# CAN_5V.net
KiCad netlist of a schematic drawn in Altium Designer
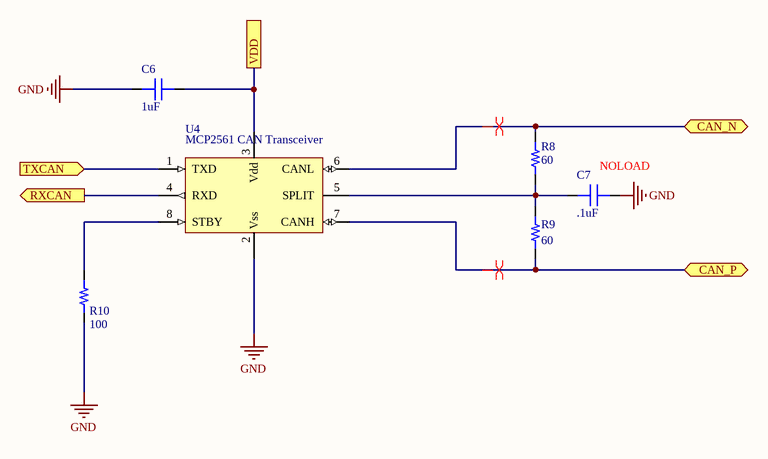
[diagram p0: CAN_5V.SchDoc]

(export (version "E")
  (design (tool "Eeschema 10.0.6"))
  (components
    (comp (ref "C6")
      (value "capacitor")
      (footprint "0603")
      (description "Generic 0603 capacitor")
      (fields (field (name "CAPACITANCE") "1uF") (field (name "VOLTAGE") "50"))
      (libsource (lib "altlib") (part "capacitor"))
    )
    (comp (ref "C7")
      (value "capacitor")
      (footprint "0603")
      (description "Generic 0603 capacitor")
      (fields (field (name "CAPACITANCE") ".1uF") (field (name "VOLTAGE") "50"))
      (libsource (lib "altlib") (part "capacitor"))
    )
    (comp (ref "R8")
      (value "60")
      (footprint "RES 0603/1608")
      (fields (field (name "RESISTANCE") "60"))
      (libsource (lib "altlib") (part "Resistor"))
    )
    (comp (ref "R9")
      (value "60")
      (footprint "RES 0603/1608")
      (fields (field (name "RESISTANCE") "60"))
      (libsource (lib "altlib") (part "Resistor"))
    )
    (comp (ref "R10")
      (value "100")
      (footprint "RES 0603/1608")
      (fields (field (name "RESISTANCE") "100"))
      (libsource (lib "altlib") (part "Resistor"))
    )
    (comp (ref "U4")
      (value "MCP2561 CAN Transceiver")
      (footprint "SOIC-8")
      (libsource (lib "altlib") (part "MCP2561 CAN Transceiver"))
    )
  )
  (nets
    (net (code "1") (name "/CAN_N") (class "Default")
      (node (ref "R8") (pin "2") (pinfunction "2_2") (pintype "passive"))
      (node (ref "U4") (pin "6") (pinfunction "CANL_6") (pintype "bidirectional"))
    )
    (net (code "2") (name "/CAN_P") (class "Default")
      (node (ref "R9") (pin "2") (pinfunction "2_2") (pintype "passive"))
      (node (ref "U4") (pin "7") (pinfunction "CANH_7") (pintype "bidirectional"))
    )
    (net (code "3") (name "/RXCAN") (class "Default")
      (node (ref "U4") (pin "4") (pinfunction "RXD_4") (pintype "output"))
    )
    (net (code "4") (name "/TXCAN") (class "Default")
      (node (ref "U4") (pin "1") (pinfunction "TXD_1") (pintype "input"))
    )
    (net (code "5") (name "/VDD") (class "Default")
      (node (ref "C6") (pin "2") (pinfunction "2_2") (pintype "passive"))
      (node (ref "U4") (pin "3") (pinfunction "Vdd_3") (pintype "passive"))
    )
    (net (code "6") (name "GND") (class "Default")
      (node (ref "C6") (pin "1") (pinfunction "1_1") (pintype "passive"))
      (node (ref "C7") (pin "2") (pinfunction "2_2") (pintype "passive"))
      (node (ref "R10") (pin "2") (pinfunction "2_2") (pintype "passive"))
      (node (ref "U4") (pin "2") (pinfunction "Vss_2") (pintype "power_in"))
    )
    (net (code "7") (name "Net-(U4-SPLIT)") (class "Default")
      (node (ref "C7") (pin "1") (pinfunction "1_1") (pintype "passive"))
      (node (ref "R8") (pin "1") (pinfunction "1_1") (pintype "passive"))
      (node (ref "R9") (pin "1") (pinfunction "1_1") (pintype "passive"))
      (node (ref "U4") (pin "5") (pinfunction "SPLIT_5") (pintype "passive"))
    )
    (net (code "8") (name "Net-(U4-STBY)") (class "Default")
      (node (ref "R10") (pin "1") (pinfunction "1_1") (pintype "passive"))
      (node (ref "U4") (pin "8") (pinfunction "STBY_8") (pintype "input"))
    )
  )
)
